# HV_BUCK_V2.net
KiCad netlist of a schematic drawn in Altium Designer
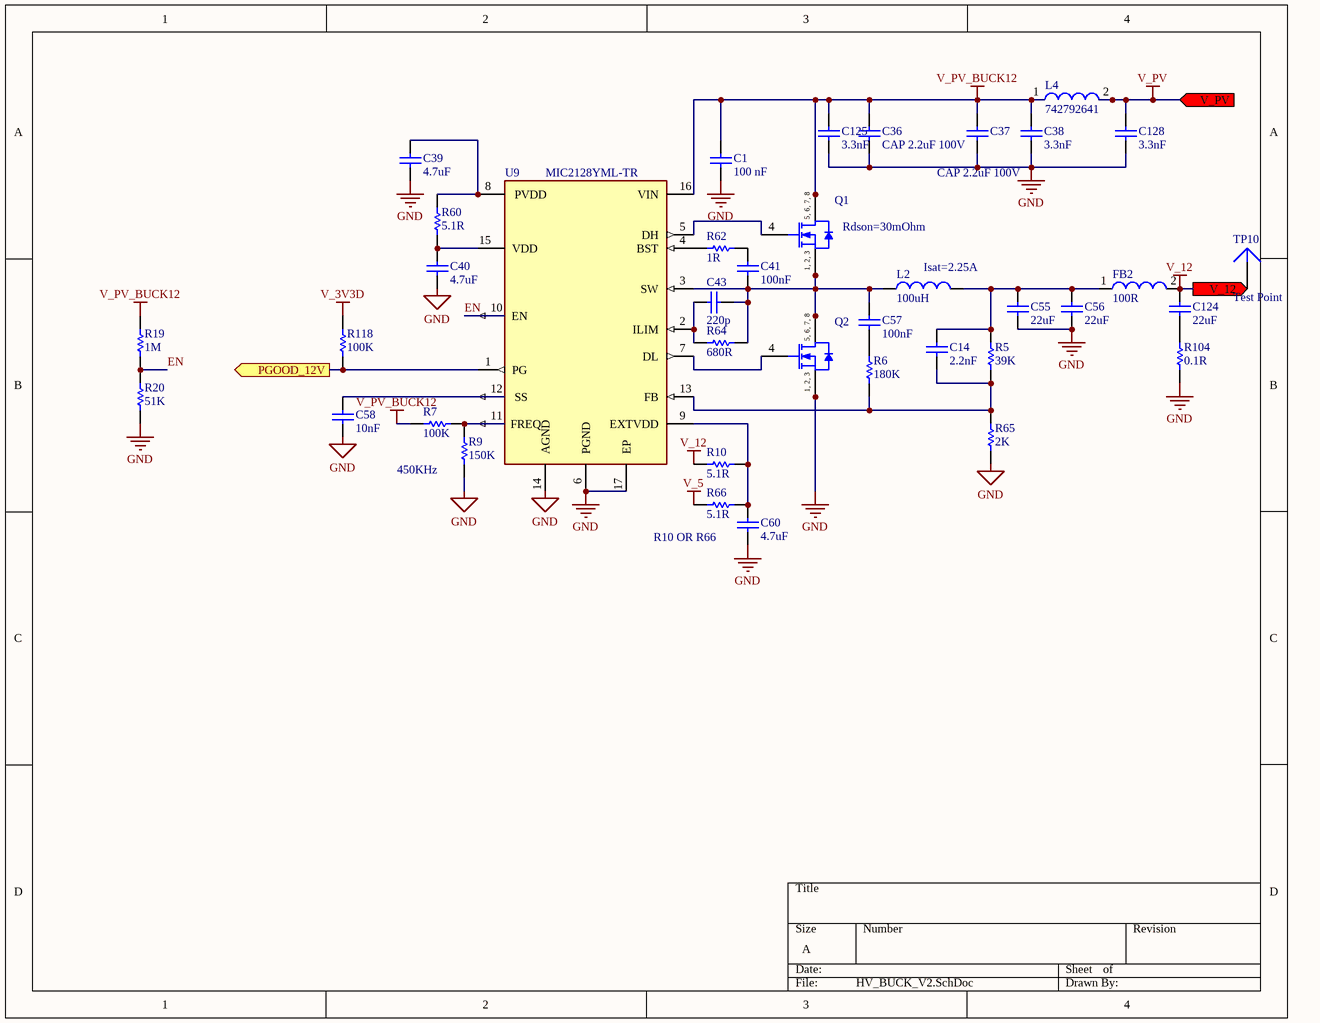
[diagram p0: HV_BUCK_V2.SchDoc]

(export (version "E")
  (design (tool "Eeschema 10.0.6"))
  (components
    (comp (ref "C1")
      (value "100 nF")
      (footprint "CAPC2013X94X50NL20T25")
      (description "X7R 100nF ±10% 100V 0805 Multilayer Ceramic Capacitors MLCC - SMD/SMT ROHS")
      (fields
        (field (name "MANUFACTURER") "AVX Interconnect / Elco")
        (field (name "PART NUMBER") "08051C104JAT2A")
      )
      (libsource (lib "DCDC") (part "CAP"))
    )
    (comp (ref "C14")
      (value "2.2nF")
      (footprint "CAPC1005X56X25NL10T15")
      (description "X7R 2.2nF ±10% 50V 0402 Multilayer Ceramic Capacitors MLCC - SMD/SMT ROHS")
      (fields
        (field (name "MANUFACTURER") "AVX Interconnect / Elco")
        (field (name "PART NUMBER") "04025C222JAT2A")
      )
      (libsource (lib "Altium Content Vault") (part "CAP"))
    )
    (comp (ref "C36")
      (value "CAP 2.2uF 100V")
      (footprint "CAPC1210(3225)280_N")
      (description "CAP 2.2uF 100V ±10% 1210 (3225 Metric) Thickness 2.8mm SMD")
      (fields (field (name "TOLERANCE") "Â±10%"))
      (libsource (lib "Altium Content Vault") (part "CAP"))
    )
    (comp (ref "C37")
      (value "CAP 2.2uF 100V")
      (footprint "CAPC1210(3225)280_N")
      (description "CAP 2.2uF 100V ±10% 1210 (3225 Metric) Thickness 2.8mm SMD")
      (fields (field (name "TOLERANCE") "Â±10%"))
      (libsource (lib "Altium Content Vault") (part "CAP"))
    )
    (comp (ref "C38")
      (value "3.3nF")
      (footprint "CAPC1608X90X35LL15T15")
      (fields
        (field (name "PART NUMBER") "06031C332KAT2A")
        (field (name "MANUFACTURER") "AVX Interconnect / Elco")
        (field (name "TOLERANCE") "10%")
      )
      (libsource (lib "Altium Content Vault") (part "CAP"))
    )
    (comp (ref "C39")
      (value "4.7uF")
      (footprint "CAPC2013X135X45LL10T25")
      (description "X5R 25V ±10% 4.7uF 0805 Multilayer Ceramic Capacitors MLCC - SMD/SMT ROHS")
      (fields (field (name "MANUFACTURER") "Murata") (field (name "PART NUMBER") "GRM21BR71H105KA12L"))
      (libsource (lib "DCDC") (part "CAP"))
    )
    (comp (ref "C40")
      (value "4.7uF")
      (footprint "CAPC2013X135X45LL10T25")
      (description "X5R 25V ±10% 4.7uF 0805 Multilayer Ceramic Capacitors MLCC - SMD/SMT ROHS")
      (fields (field (name "MANUFACTURER") "Murata") (field (name "PART NUMBER") "GRM21BR71H105KA12L"))
      (libsource (lib "DCDC") (part "CAP"))
    )
    (comp (ref "C41")
      (value "100nF")
      (footprint "CAPC1005X56X25NL10T15")
      (description "X7R 100nF ±10% 16V 0402 Multilayer Ceramic Capacitors MLCC - SMD/SMT ROHS")
      (fields
        (field (name "MANUFACTURER") "AVX Interconnect / Elco")
        (field (name "PART NUMBER") "0402YC104KAT2A")
      )
      (libsource (lib "Altium Content Vault") (part "CAP"))
    )
    (comp (ref "C43")
      (value "220p")
      (footprint "CAPC1005X56X25NL10T15")
      (description "X7R 220pF ±10% 50V 0402 Multilayer Ceramic Capacitors MLCC - SMD/SMT ROHS")
      (fields
        (field (name "MANUFACTURER") "AVX Interconnect / Elco")
        (field (name "PART NUMBER") "04025C222JAT2A")
      )
      (libsource (lib "DCDC") (part "CAP"))
    )
    (comp (ref "C55")
      (value "22uF")
      (footprint "CAPC3225X279X50NL20T25")
      (description "Ceramic Capacitor, 25 V, 22 uF, +/-10%, -55 to 85 degC, 2-Pin SMD (1210), RoHS, Tape and Reel")
      (fields (field (name "TOLERANCE") "10%") (field (name "MANUFACTURER") "AVX"))
      (libsource (lib "Altium Content Vault") (part "CAP-NP-2"))
    )
    (comp (ref "C56")
      (value "22uF")
      (footprint "CAPC3225X279X50NL20T25")
      (description "Ceramic Capacitor, 25 V, 22 uF, +/-10%, -55 to 85 degC, 2-Pin SMD (1210), RoHS, Tape and Reel")
      (fields (field (name "TOLERANCE") "10%") (field (name "MANUFACTURER") "AVX"))
      (libsource (lib "Altium Content Vault") (part "CAP-NP-2"))
    )
    (comp (ref "C57")
      (value "100nF")
      (footprint "CAPC1608X90X35NL10T15")
      (description "X7R 100nF ±10% 50V 0603 Multilayer Ceramic Capacitors MLCC - SMD/SMT ROHS")
      (fields (field (name "PART NUMBER") "GCM188R72A104KA64D") (field (name "MANUFACTURER") "Murata"))
      (libsource (lib "DCDC") (part "CAP"))
    )
    (comp (ref "C58")
      (value "10nF")
      (footprint "CAPC1005X56X25NL10T15")
      (description "X7R ±10% 50V 10nF 0603 Multilayer Ceramic Capacitors MLCC - SMD/SMT ROHS")
      (fields
        (field (name "MANUFACTURER") "AVX Interconnect / Elco")
        (field (name "PART NUMBER") "04023C103JAT2A")
      )
      (libsource (lib "Altium Content Vault") (part "CAP"))
    )
    (comp (ref "C60")
      (value "4.7uF")
      (footprint "CAPC2013X135X45LL10T25")
      (description "X5R 25V ±10% 4.7uF 0805 Multilayer Ceramic Capacitors MLCC - SMD/SMT ROHS")
      (fields (field (name "MANUFACTURER") "Murata") (field (name "PART NUMBER") "GRM21BR71H105KA12L"))
      (libsource (lib "Altium Content Vault") (part "CAP"))
    )
    (comp (ref "C124")
      (value "22uF")
      (footprint "CAPC3225X279X50NL20T25")
      (description "Ceramic Capacitor, 25 V, 22 uF, +/-10%, -55 to 85 degC, 2-Pin SMD (1210), RoHS, Tape and Reel")
      (fields (field (name "TOLERANCE") "10%") (field (name "MANUFACTURER") "AVX"))
      (libsource (lib "Altium Content Vault") (part "CAP-NP-2"))
    )
    (comp (ref "C125")
      (value "3.3nF")
      (footprint "CAPC1608X90X35LL15T15")
      (fields
        (field (name "PART NUMBER") "06031C332KAT2A")
        (field (name "MANUFACTURER") "AVX Interconnect / Elco")
        (field (name "TOLERANCE") "10%")
      )
      (libsource (lib "Altium Content Vault") (part "CAP"))
    )
    (comp (ref "C128")
      (value "3.3nF")
      (footprint "CAPC1608X90X35LL15T15")
      (fields
        (field (name "PART NUMBER") "06031C332KAT2A")
        (field (name "MANUFACTURER") "AVX Interconnect / Elco")
        (field (name "TOLERANCE") "10%")
      )
      (libsource (lib "Altium Content Vault") (part "CAP"))
    )
    (comp (ref "FB2")
      (value "100R")
      (footprint "SMD-0603")
      (description "SMD EMI Suppression Ferrite Bead WE-CBF, Z = 1500 Ohm")
      (libsource (lib "Altium Content Vault") (part "PAS-IND-INDUCTOR-2"))
    )
    (comp (ref "L2")
      (value "100uH")
      (footprint "VISH-IHLP4040DZER101M11_V")
      (fields
        (field (name "MANUFACTURER") "Vishay")
        (field (name "TOLERANCE") "20%")
        (field (name "MANUFACTURER PART NUMBER") "IHLP4040DZER101M11")
      )
      (libsource (lib "Altium Content Vault") (part "IND-2"))
    )
    (comp (ref "L4")
      (value "742792641")
      (footprint "RESC2012X70N")
      (description "SMD EMI Suppression Ferrite Bead WE-CBF, Z = 300 Ohm")
      (fields (field (name "MANUFACTURER") "Wurth Electronics") (field (name "TOLERANCE") "25%"))
      (libsource (lib "PBL - Resistors") (part "PAS-IND-INDUCTOR-2"))
    )
    (comp (ref "Q1")
      (value "IAUZ20N08S5L300")
      (footprint "INF-PG-TSDSON-8-1_V")
      (fields (field (name "MANUFACTURER") "Infineon"))
      (libsource (lib "Altium Content Vault") (part "INF-NEMOS-SSSGDDDD-8"))
    )
    (comp (ref "Q2")
      (value "IAUZ20N08S5L300")
      (footprint "INF-PG-TSDSON-8-1_V")
      (fields (field (name "MANUFACTURER") "Infineon"))
      (libsource (lib "Altium Content Vault") (part "INF-NEMOS-SSSGDDDD-8"))
    )
    (comp (ref "R5")
      (value "39K")
      (footprint "RESC1005X40X25NL05T10")
      (description "±1% 39kΩ 1/16W ±100ppm/℃ 0402 Chip Resistor - Surface Mount ROHS")
      (fields (field (name "MANUFACTURER") "Yageo / Phycomp") (field (name "PART NUMBER") "RC0402FR-0719K1L"))
      (libsource (lib "Altium Content Vault") (part "RES"))
    )
    (comp (ref "R6")
      (value "180K")
      (footprint "RESC1608X55X30NL15T15")
      (description "±1% 180kΩ ±100ppm/℃ 0.1W 0603 Chip Resistor - Surface Mount ROHS")
      (fields (field (name "PART NUMBER") "ERJ3EKF1803V") (field (name "MANUFACTURER") "Panasonic"))
      (libsource (lib "Altium Content Vault") (part "RES"))
    )
    (comp (ref "R7")
      (value "100K")
      (footprint "RESC1608X55X25NL10T15")
      (description "±1% 100kΩ ±100ppm/℃ 0.1W 0603 Chip Resistor - Surface Mount ROHS")
      (fields (field (name "MANUFACTURER") "Yageo") (field (name "TOLERANCE") "1%"))
      (libsource (lib "Altium Content Vault") (part "RES-2"))
    )
    (comp (ref "R9")
      (value "150K")
      (footprint "RESC1608X55X25NL10T15")
      (description "150kΩ ±1% ±100ppm/℃ 0.1W 0603 Chip Resistor - Surface Mount ROHS")
      (fields
        (field (name "MANUFACTURER") "Yageo")
        (field (name "MANUFACTURER PART NUMBER") "RC0603FR-07150KL")
      )
      (libsource (lib "Altium Content Vault") (part "RES-2"))
    )
    (comp (ref "R10")
      (value "5.1R")
      (footprint "RESC1608X55X30NL15T15")
      (description "±1% ±400ppm/℃ 5.1Ω 0.1W 0603 Chip Resistor - Surface Mount ROHS")
      (fields (field (name "PART NUMBER") "ERJ3EKF1803V") (field (name "MANUFACTURER") "Panasonic"))
      (libsource (lib "DCDC") (part "RES"))
    )
    (comp (ref "R19")
      (value "1M")
      (footprint "RESC1608X55X25NL10T15")
      (description "1MΩ ±1% ±100ppm/℃ 0.1W 0603 Chip Resistor - Surface Mount ROHS")
      (fields (field (name "MANUFACTURER") "Yageo") (field (name "PART NUMBER") "AC0603FR-071ML"))
      (libsource (lib "Altium Content Vault") (part "RES"))
    )
    (comp (ref "R20")
      (value "51K")
      (footprint "RESC1608X55X25NL10T15")
      (description "±1% 51kΩ ±100ppm/℃ 0.1W 0603 Chip Resistor - Surface Mount ROHS")
      (fields (field (name "MANUFACTURER") "Yageo") (field (name "TOLERANCE") "1%"))
      (libsource (lib "Altium Content Vault") (part "RES-2"))
    )
    (comp (ref "R60")
      (value "5.1R")
      (footprint "RESC1608X55X30NL15T15")
      (description "±1% ±400ppm/℃ 5.1Ω 0.1W 0603 Chip Resistor - Surface Mount ROHS")
      (fields (field (name "PART NUMBER") "ERJ3EKF1803V") (field (name "MANUFACTURER") "Panasonic"))
      (libsource (lib "DCDC") (part "RES"))
    )
    (comp (ref "R62")
      (value "1R")
      (footprint "RESC1005X40X25NL05T10")
      (description "±1% ±400ppm/℃ 1Ω 1/16W 0402 Chip Resistor - Surface Mount ROHS")
      (fields (field (name "MANUFACTURER") "Yageo / Phycomp") (field (name "PART NUMBER") "RC0402FR-073R3L"))
      (libsource (lib "Altium Content Vault") (part "RES"))
    )
    (comp (ref "R64")
      (value "680R")
      (footprint "RESC1005X40X25NL05T10")
      (description "RC-L Series 0402 680 Ohm 0.063 W ±1% ±100 ppm/°C SMT Thick Film Chip Resistor")
      (fields (field (name "MANUFACTURER") "Yageo / Phycomp") (field (name "PART NUMBER") "RC0402FR-07953RL"))
      (libsource (lib "Altium Content Vault") (part "RES"))
    )
    (comp (ref "R65")
      (value "2K")
      (footprint "RESC1005X40X25NL05T10")
      (description "1/16W ±1% 2kΩ ±100ppm/℃ 0402 Chip Resistor - Surface Mount ROHS")
      (fields (field (name "PART NUMBER") "RC0402FR-071KL") (field (name "MANUFACTURER") "Yageo / Phycomp"))
      (libsource (lib "Altium Content Vault") (part "RES"))
    )
    (comp (ref "R66")
      (value "5.1R")
      (footprint "RESC1608X55X30NL15T15")
      (description "±1% ±400ppm/℃ 5.1Ω 0.1W 0603 Chip Resistor - Surface Mount ROHS")
      (fields (field (name "PART NUMBER") "ERJ3EKF1803V") (field (name "MANUFACTURER") "Panasonic"))
      (libsource (lib "DCDC") (part "RES"))
    )
    (comp (ref "R104")
      (value "0.1R")
      (footprint "RESC1608X55X25ML10T15")
      (description "Chip Resistor, 0 Ohm, +/- 5%, 0.1 W, -55 to 155 degC, 0603 (1608 Metric), RoHS, Tape and Reel")
      (fields (field (name "TOLERANCE") "5%") (field (name "MANUFACTURER") "Yageo"))
      (libsource (lib "Altium Content Vault") (part "RES-2"))
    )
    (comp (ref "R118")
      (value "100K")
      (footprint "RESC1608X55X25NL10T15")
      (description "±1% 100kΩ ±100ppm/℃ 0.1W 0603 Chip Resistor - Surface Mount ROHS")
      (fields (field (name "MANUFACTURER") "Yageo") (field (name "TOLERANCE") "1%"))
      (libsource (lib "DCDC") (part "CMP-2100-03662-1"))
    )
    (comp (ref "TP10")
      (value "Test Point")
      (footprint "TP1.5mm")
      (description "Round Test Point")
      (fields (field (name "PUBLISHER") "Altium Limited"))
      (libsource (lib "DCDC") (part "Test_Point 1.5mm round"))
    )
    (comp (ref "U9")
      (value "MIC2128YML-TR")
      (footprint "SamacSys:QFN50P300X300X90-17N")
      (description "Integrated Circuit")
      (fields (field (name "MOUSER PART NUMBER") "579-MIC2128YML-TR"))
      (libsource (lib "SamacSys") (part "MIC2128YML-TR"))
    )
  )
  (nets
    (net (code "1") (name "/EN") (class "Default")
      (node (ref "R19") (pin "1") (pinfunction "1_1") (pintype "passive"))
      (node (ref "R20") (pin "2") (pinfunction "2_2") (pintype "passive"))
      (node (ref "U9") (pin "10") (pinfunction "EN_10") (pintype "input"))
    )
    (net (code "2") (name "/PGOOD_12V") (class "Default")
      (node (ref "R118") (pin "1") (pinfunction "1_1") (pintype "passive"))
      (node (ref "U9") (pin "1") (pinfunction "PG_1") (pintype "output"))
    )
    (net (code "3") (name "GND") (class "Default")
      (node (ref "C1") (pin "1") (pinfunction "1_1") (pintype "passive"))
      (node (ref "C125") (pin "1") (pinfunction "1_1") (pintype "passive"))
      (node (ref "C128") (pin "1") (pinfunction "1_1") (pintype "passive"))
      (node (ref "C36") (pin "1") (pinfunction "1_1") (pintype "passive"))
      (node (ref "C37") (pin "1") (pinfunction "1_1") (pintype "passive"))
      (node (ref "C38") (pin "1") (pinfunction "1_1") (pintype "passive"))
      (node (ref "C39") (pin "1") (pinfunction "1_1") (pintype "passive"))
      (node (ref "C40") (pin "1") (pinfunction "1_1") (pintype "passive"))
      (node (ref "C55") (pin "1") (pinfunction "1_1") (pintype "passive"))
      (node (ref "C56") (pin "1") (pinfunction "1_1") (pintype "passive"))
      (node (ref "C58") (pin "1") (pinfunction "1_1") (pintype "passive"))
      (node (ref "C60") (pin "1") (pinfunction "1_1") (pintype "passive"))
      (node (ref "Q2") (pin "1") (pinfunction "SOURCE_1") (pintype "passive"))
      (node (ref "Q2") (pin "2") (pinfunction "SOURCE_2") (pintype "passive"))
      (node (ref "Q2") (pin "3") (pinfunction "SOURCE_3") (pintype "passive"))
      (node (ref "R104") (pin "1") (pinfunction "1_1") (pintype "passive"))
      (node (ref "R20") (pin "1") (pinfunction "1_1") (pintype "passive"))
      (node (ref "R65") (pin "1") (pinfunction "1_1") (pintype "passive"))
      (node (ref "R9") (pin "1") (pinfunction "1_1") (pintype "passive"))
      (node (ref "U9") (pin "14") (pinfunction "AGND_14") (pintype "power_in"))
      (node (ref "U9") (pin "17") (pinfunction "EP_17") (pintype "power_in"))
      (node (ref "U9") (pin "6") (pinfunction "PGND_6") (pintype "power_in"))
    )
    (net (code "4") (name "Net-(C14-Pad2)") (class "Default")
      (node (ref "C14") (pin "2") (pinfunction "2_2") (pintype "passive"))
      (node (ref "C55") (pin "2") (pinfunction "2_2") (pintype "passive"))
      (node (ref "C56") (pin "2") (pinfunction "2_2") (pintype "passive"))
      (node (ref "FB2") (pin "1") (pinfunction "1_1") (pintype "passive"))
      (node (ref "L2") (pin "2") (pinfunction "2_2") (pintype "passive"))
      (node (ref "R5") (pin "2") (pinfunction "2_2") (pintype "passive"))
    )
    (net (code "5") (name "Net-(C41-Pad2)") (class "Default")
      (node (ref "C41") (pin "2") (pinfunction "2_2") (pintype "passive"))
      (node (ref "R62") (pin "1") (pinfunction "1_1") (pintype "passive"))
    )
    (net (code "6") (name "Net-(C57-Pad1)") (class "Default")
      (node (ref "C57") (pin "1") (pinfunction "1_1") (pintype "passive"))
      (node (ref "R6") (pin "2") (pinfunction "2_2") (pintype "passive"))
    )
    (net (code "7") (name "Net-(C124-Pad1)") (class "Default")
      (node (ref "C124") (pin "1") (pinfunction "1_1") (pintype "passive"))
      (node (ref "R104") (pin "2") (pinfunction "2_2") (pintype "passive"))
    )
    (net (code "8") (name "Net-(Q1-GATE)") (class "Default")
      (node (ref "Q1") (pin "4") (pinfunction "GATE_4") (pintype "passive"))
      (node (ref "U9") (pin "5") (pinfunction "DH_5") (pintype "output"))
    )
    (net (code "9") (name "Net-(Q2-GATE)") (class "Default")
      (node (ref "Q2") (pin "4") (pinfunction "GATE_4") (pintype "passive"))
      (node (ref "U9") (pin "7") (pinfunction "DL_7") (pintype "output"))
    )
    (net (code "10") (name "Net-(U9-BST)") (class "Default")
      (node (ref "R62") (pin "2") (pinfunction "2_2") (pintype "passive"))
      (node (ref "U9") (pin "4") (pinfunction "BST_4") (pintype "input"))
    )
    (net (code "11") (name "Net-(U9-EXTVDD)") (class "Default")
      (node (ref "C60") (pin "2") (pinfunction "2_2") (pintype "passive"))
      (node (ref "R10") (pin "1") (pinfunction "1_1") (pintype "passive"))
      (node (ref "R66") (pin "1") (pinfunction "1_1") (pintype "passive"))
      (node (ref "U9") (pin "9") (pinfunction "EXTVDD_9") (pintype "power_in"))
    )
    (net (code "12") (name "Net-(U9-FB)") (class "Default")
      (node (ref "C14") (pin "1") (pinfunction "1_1") (pintype "passive"))
      (node (ref "R5") (pin "1") (pinfunction "1_1") (pintype "passive"))
      (node (ref "R6") (pin "1") (pinfunction "1_1") (pintype "passive"))
      (node (ref "R65") (pin "2") (pinfunction "2_2") (pintype "passive"))
      (node (ref "U9") (pin "13") (pinfunction "FB_13") (pintype "input"))
    )
    (net (code "13") (name "Net-(U9-FREQ)") (class "Default")
      (node (ref "R7") (pin "2") (pinfunction "2_2") (pintype "passive"))
      (node (ref "R9") (pin "2") (pinfunction "2_2") (pintype "passive"))
      (node (ref "U9") (pin "11") (pinfunction "FREQ_11") (pintype "input"))
    )
    (net (code "14") (name "Net-(U9-ILIM)") (class "Default")
      (node (ref "C43") (pin "2") (pinfunction "2_2") (pintype "passive"))
      (node (ref "R64") (pin "2") (pinfunction "2_2") (pintype "passive"))
      (node (ref "U9") (pin "2") (pinfunction "ILIM_2") (pintype "input"))
    )
    (net (code "15") (name "Net-(U9-PVDD)") (class "Default")
      (node (ref "C39") (pin "2") (pinfunction "2_2") (pintype "passive"))
      (node (ref "R60") (pin "2") (pinfunction "2_2") (pintype "passive"))
      (node (ref "U9") (pin "8") (pinfunction "PVDD_8") (pintype "power_in"))
    )
    (net (code "16") (name "Net-(U9-SS)") (class "Default")
      (node (ref "C58") (pin "2") (pinfunction "2_2") (pintype "passive"))
      (node (ref "U9") (pin "12") (pinfunction "SS_12") (pintype "input"))
    )
    (net (code "17") (name "Net-(U9-SW)") (class "Default")
      (node (ref "C41") (pin "1") (pinfunction "1_1") (pintype "passive"))
      (node (ref "C43") (pin "1") (pinfunction "1_1") (pintype "passive"))
      (node (ref "C57") (pin "2") (pinfunction "2_2") (pintype "passive"))
      (node (ref "L2") (pin "1") (pinfunction "1_1") (pintype "passive"))
      (node (ref "Q1") (pin "1") (pinfunction "SOURCE_1") (pintype "passive"))
      (node (ref "Q1") (pin "2") (pinfunction "SOURCE_2") (pintype "passive"))
      (node (ref "Q1") (pin "3") (pinfunction "SOURCE_3") (pintype "passive"))
      (node (ref "Q2") (pin "5") (pinfunction "DRAIN_5") (pintype "passive"))
      (node (ref "Q2") (pin "6") (pinfunction "DRAIN_6") (pintype "passive"))
      (node (ref "Q2") (pin "7") (pinfunction "DRAIN_7") (pintype "passive"))
      (node (ref "Q2") (pin "8") (pinfunction "DRAIN_8") (pintype "passive"))
      (node (ref "R64") (pin "1") (pinfunction "1_1") (pintype "passive"))
      (node (ref "U9") (pin "3") (pinfunction "SW_3") (pintype "input"))
    )
    (net (code "18") (name "Net-(U9-VDD)") (class "Default")
      (node (ref "C40") (pin "2") (pinfunction "2_2") (pintype "passive"))
      (node (ref "R60") (pin "1") (pinfunction "1_1") (pintype "passive"))
      (node (ref "U9") (pin "15") (pinfunction "VDD_15") (pintype "power_in"))
    )
    (net (code "19") (name "V_3V3D") (class "Default")
      (node (ref "R118") (pin "2") (pinfunction "2_2") (pintype "passive"))
    )
    (net (code "20") (name "V_5") (class "Default")
      (node (ref "R66") (pin "2") (pinfunction "2_2") (pintype "passive"))
    )
    (net (code "21") (name "V_12") (class "Default")
      (node (ref "C124") (pin "2") (pinfunction "2_2") (pintype "passive"))
      (node (ref "FB2") (pin "2") (pinfunction "2_2") (pintype "passive"))
      (node (ref "R10") (pin "2") (pinfunction "2_2") (pintype "passive"))
      (node (ref "TP10") (pin "1") (pinfunction "1_1") (pintype "passive"))
    )
    (net (code "22") (name "V_PV") (class "Default")
      (node (ref "C128") (pin "2") (pinfunction "2_2") (pintype "passive"))
      (node (ref "L4") (pin "2") (pinfunction "2_2") (pintype "passive"))
    )
    (net (code "23") (name "V_PV_BUCK12") (class "Default")
      (node (ref "C1") (pin "2") (pinfunction "2_2") (pintype "passive"))
      (node (ref "C125") (pin "2") (pinfunction "2_2") (pintype "passive"))
      (node (ref "C36") (pin "2") (pinfunction "2_2") (pintype "passive"))
      (node (ref "C37") (pin "2") (pinfunction "2_2") (pintype "passive"))
      (node (ref "C38") (pin "2") (pinfunction "2_2") (pintype "passive"))
      (node (ref "L4") (pin "1") (pinfunction "1_1") (pintype "passive"))
      (node (ref "Q1") (pin "5") (pinfunction "DRAIN_5") (pintype "passive"))
      (node (ref "Q1") (pin "6") (pinfunction "DRAIN_6") (pintype "passive"))
      (node (ref "Q1") (pin "7") (pinfunction "DRAIN_7") (pintype "passive"))
      (node (ref "Q1") (pin "8") (pinfunction "DRAIN_8") (pintype "passive"))
      (node (ref "R19") (pin "2") (pinfunction "2_2") (pintype "passive"))
      (node (ref "R7") (pin "1") (pinfunction "1_1") (pintype "passive"))
      (node (ref "U9") (pin "16") (pinfunction "VIN_16") (pintype "power_in"))
    )
  )
)
